# in_out_ports.net
KiCad netlist of a schematic drawn in Altium Designer
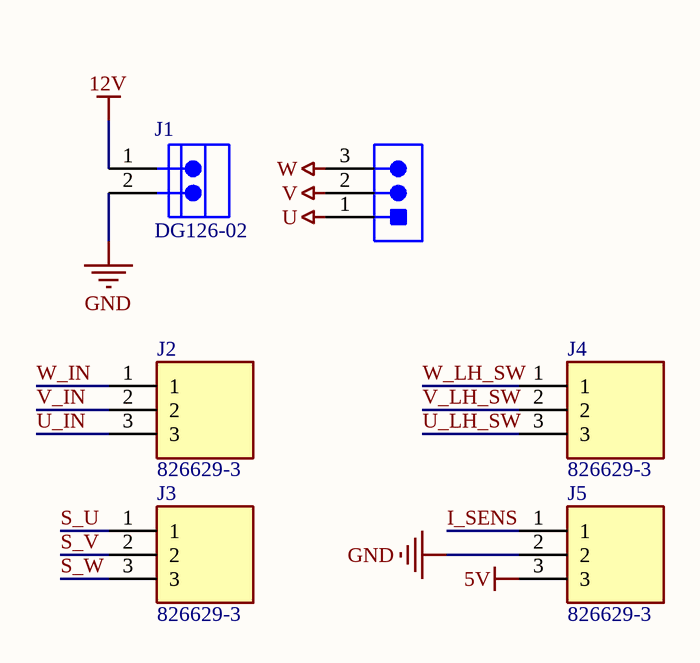
[diagram p0: in_out_ports.SchDoc]

(export (version "E")
  (design (tool "Eeschema 10.0.6"))
  (components
    (comp (ref "J1")
      (value "DG126-02")
      (footprint "CXKF-KF129C-2_V")
      (fields
        (field (name "PARTNUMBER") "KF129C-02P-14")
        (field (name "MANUFACTURER") "Cixi KaiFeng")
        (field (name "CONTACT") "Brass")
      )
      (libsource (lib "Altium Content Vault") (part "CXKF-KF129C-2"))
    )
    (comp (ref "J2")
      (value "826629-3")
      (footprint "SamacSys:HDRV3W63P0X254_1X3_762X250X950P")
      (description "Connector")
      (fields (field (name "MOUSER PART NUMBER") "571-826629-3"))
      (libsource (lib "*") (part "826629-3"))
    )
    (comp (ref "J3")
      (value "826629-3")
      (footprint "SamacSys:HDRV3W63P0X254_1X3_762X250X950P")
      (description "Connector")
      (fields (field (name "MOUSER PART NUMBER") "571-826629-3"))
      (libsource (lib "*") (part "826629-3"))
    )
    (comp (ref "J4")
      (value "826629-3")
      (footprint "SamacSys:HDRV3W63P0X254_1X3_762X250X950P")
      (description "Connector")
      (fields (field (name "MOUSER PART NUMBER") "571-826629-3"))
      (libsource (lib "*") (part "826629-3"))
    )
    (comp (ref "J5")
      (value "826629-3")
      (footprint "SamacSys:HDRV3W63P0X254_1X3_762X250X950P")
      (description "Connector")
      (fields (field (name "MOUSER PART NUMBER") "571-826629-3"))
      (libsource (lib "*") (part "826629-3"))
    )
    (comp (ref "MOTOR")
      (value "SCREW-5.0/5.08 3WAYS")
      (footprint "SCREW-5.0-3WAYS_V")
      (description "Socket, Screw Terminal Block, 3 Way, 5.0 mm Pitch, 90 Degree Angle, Through-Hole")
      (fields (field (name "MANUFACTURER") "No Vendor"))
      (libsource (lib "Altium Content Vault") (part "SCREW-3WAYS"))
    )
  )
  (nets
    (net (code "1") (name "/I_SENS") (class "Default")
      (node (ref "J5") (pin "1") (pinfunction "1_1") (pintype "passive"))
    )
    (net (code "2") (name "/S_U") (class "Default")
      (node (ref "J3") (pin "1") (pinfunction "1_1") (pintype "passive"))
    )
    (net (code "3") (name "/S_V") (class "Default")
      (node (ref "J3") (pin "2") (pinfunction "2_2") (pintype "passive"))
    )
    (net (code "4") (name "/S_W") (class "Default")
      (node (ref "J3") (pin "3") (pinfunction "3_3") (pintype "passive"))
    )
    (net (code "5") (name "/U_IN") (class "Default")
      (node (ref "J2") (pin "3") (pinfunction "3_3") (pintype "passive"))
    )
    (net (code "6") (name "/U_LH_SW") (class "Default")
      (node (ref "J4") (pin "3") (pinfunction "3_3") (pintype "passive"))
    )
    (net (code "7") (name "/V_IN") (class "Default")
      (node (ref "J2") (pin "2") (pinfunction "2_2") (pintype "passive"))
    )
    (net (code "8") (name "/V_LH_SW") (class "Default")
      (node (ref "J4") (pin "2") (pinfunction "2_2") (pintype "passive"))
    )
    (net (code "9") (name "/W_IN") (class "Default")
      (node (ref "J2") (pin "1") (pinfunction "1_1") (pintype "passive"))
    )
    (net (code "10") (name "/W_LH_SW") (class "Default")
      (node (ref "J4") (pin "1") (pinfunction "1_1") (pintype "passive"))
    )
    (net (code "11") (name "5V") (class "Default")
      (node (ref "J5") (pin "3") (pinfunction "3_3") (pintype "passive"))
    )
    (net (code "12") (name "12V") (class "Default")
      (node (ref "J1") (pin "1") (pinfunction "1_1") (pintype "passive"))
    )
    (net (code "13") (name "GND") (class "Default")
      (node (ref "J1") (pin "2") (pinfunction "2_2") (pintype "passive"))
      (node (ref "J5") (pin "2") (pinfunction "2_2") (pintype "passive"))
    )
    (net (code "14") (name "U") (class "Default")
      (node (ref "MOTOR") (pin "1") (pinfunction "1_1") (pintype "passive"))
    )
    (net (code "15") (name "V") (class "Default")
      (node (ref "MOTOR") (pin "2") (pinfunction "2_2") (pintype "passive"))
    )
    (net (code "16") (name "W") (class "Default")
      (node (ref "MOTOR") (pin "3") (pinfunction "3_3") (pintype "passive"))
    )
  )
)
